# LoRa_ST_v1_0.net
KiCad netlist of a schematic drawn in EAGLE
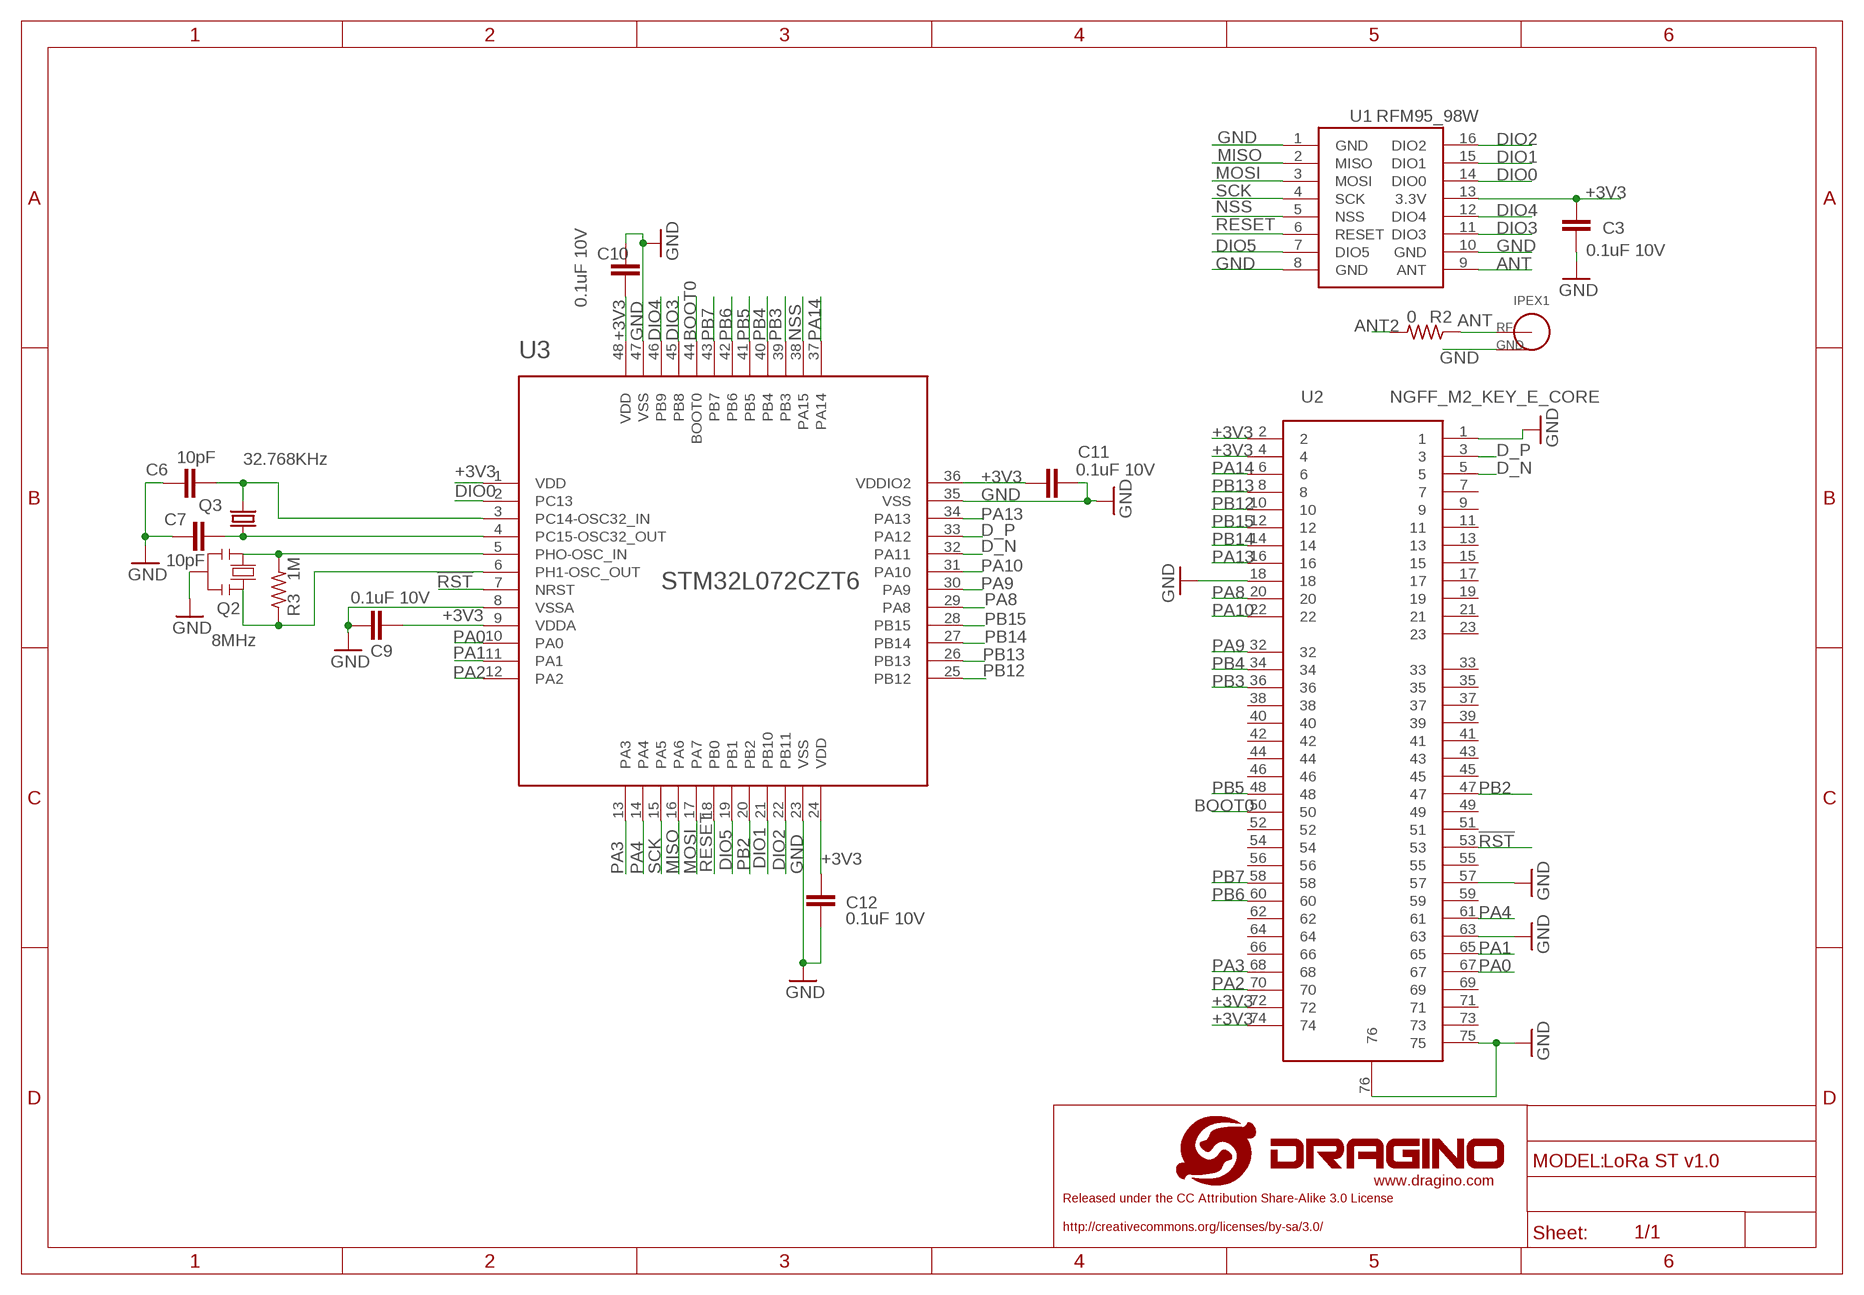
[diagram p0: schematic, sheet 1]

(export (version "E")
  (design (tool "Eeschema 10.0.6"))
  (components
    (comp (ref "C3")
      (value "0.1uF 10V")
      (footprint "eagle-import:C0402")
      (libsource (lib "eagle-import") (part "C-EUC0402"))
    )
    (comp (ref "C6")
      (value "10pF")
      (footprint "eagle-import:C0402")
      (libsource (lib "eagle-import") (part "C-EUC0402"))
    )
    (comp (ref "C7")
      (value "10pF")
      (footprint "eagle-import:C0402")
      (libsource (lib "eagle-import") (part "C-EUC0402"))
    )
    (comp (ref "C9")
      (value "0.1uF 10V")
      (footprint "eagle-import:C0402")
      (libsource (lib "eagle-import") (part "C-EUC0402"))
    )
    (comp (ref "C10")
      (value "0.1uF 10V")
      (footprint "eagle-import:C0402")
      (libsource (lib "eagle-import") (part "C-EUC0402"))
    )
    (comp (ref "C11")
      (value "0.1uF 10V")
      (footprint "eagle-import:C0402")
      (libsource (lib "eagle-import") (part "C-EUC0402"))
    )
    (comp (ref "C12")
      (value "0.1uF 10V")
      (footprint "eagle-import:C0402")
      (libsource (lib "eagle-import") (part "C-EUC0402"))
    )
    (comp (ref "IPEX1")
      (value "I-PEX4")
      (footprint "eagle-import:I-PEX4")
      (libsource (lib "eagle-import") (part "I-PEX4"))
    )
    (comp (ref "Q2")
      (value "8MHz")
      (footprint "eagle-import:RESONATOR")
      (libsource (lib "eagle-import") (part "RESONATORMU"))
    )
    (comp (ref "Q3")
      (value "32.768KHz")
      (footprint "eagle-import:32.768K")
      (libsource (lib "eagle-import") (part "SMD-2012_2P"))
    )
    (comp (ref "R2")
      (value "0")
      (footprint "eagle-import:R0402")
      (libsource (lib "eagle-import") (part "R-US_R0402"))
    )
    (comp (ref "R3")
      (value "1M")
      (footprint "eagle-import:R0402")
      (libsource (lib "eagle-import") (part "R-US_R0402"))
    )
    (comp (ref "U$2")
      (value "LOGO-NEW")
      (footprint "eagle-import:LOGO-SILK-NEW")
      (libsource (lib "eagle-import") (part "LOGO-NEW"))
    )
    (comp (ref "U1")
      (value "RFM95_98W")
      (footprint "eagle-import:RFM95_98W")
      (libsource (lib "eagle-import") (part "RFM95_98W"))
    )
    (comp (ref "U2")
      (value "NGFF_M2_KEY_E_CORE")
      (footprint "eagle-import:LORA_ST_PCB")
      (libsource (lib "eagle-import") (part "NGFF_M2_KEY_E_CORE"))
    )
    (comp (ref "U3")
      (value "STM32L072CZT6")
      (footprint "eagle-import:LQFP48")
      (libsource (lib "eagle-import") (part "STM32L0XX"))
    )
  )
  (nets
    (net (code "1") (name "/+3V3") (class "Default")
      (node (ref "C10") (pin "1") (pinfunction "1_1") (pintype "passive"))
      (node (ref "C11") (pin "2") (pinfunction "2_2") (pintype "passive"))
      (node (ref "C12") (pin "2") (pinfunction "2_2") (pintype "passive"))
      (node (ref "C3") (pin "2") (pinfunction "2_2") (pintype "passive"))
      (node (ref "C9") (pin "1") (pinfunction "1_1") (pintype "passive"))
      (node (ref "U1") (pin "13") (pinfunction "3.3V_13") (pintype "power_in"))
      (node (ref "U2") (pin "2") (pinfunction "2_2") (pintype "bidirectional"))
      (node (ref "U2") (pin "4") (pinfunction "4_4") (pintype "bidirectional"))
      (node (ref "U2") (pin "72") (pinfunction "72_72") (pintype "bidirectional"))
      (node (ref "U2") (pin "74") (pinfunction "74_74") (pintype "bidirectional"))
      (node (ref "U3") (pin "1") (pinfunction "VDD_1") (pintype "bidirectional"))
      (node (ref "U3") (pin "24") (pinfunction "VDD_24") (pintype "bidirectional"))
      (node (ref "U3") (pin "36") (pinfunction "VDDIO2_36") (pintype "bidirectional"))
      (node (ref "U3") (pin "48") (pinfunction "VDD_48") (pintype "bidirectional"))
      (node (ref "U3") (pin "9") (pinfunction "VDDA_9") (pintype "bidirectional"))
    )
    (net (code "2") (name "/ANT") (class "Default")
      (node (ref "IPEX1") (pin "SIG") (pinfunction "SIG_SIG") (pintype "passive"))
      (node (ref "R2") (pin "1") (pinfunction "1_1") (pintype "passive"))
      (node (ref "U1") (pin "9") (pinfunction "ANT_9") (pintype "bidirectional"))
    )
    (net (code "3") (name "/ANT2") (class "Default")
      (node (ref "R2") (pin "2") (pinfunction "2_2") (pintype "passive"))
    )
    (net (code "4") (name "/BOOT0") (class "Default")
      (node (ref "U2") (pin "50") (pinfunction "50_50") (pintype "bidirectional"))
      (node (ref "U3") (pin "44") (pinfunction "BOOT0_44") (pintype "bidirectional"))
    )
    (net (code "5") (name "/DIO0") (class "Default")
      (node (ref "U1") (pin "14") (pinfunction "DIO0_14") (pintype "bidirectional"))
      (node (ref "U3") (pin "2") (pinfunction "PC13_2") (pintype "bidirectional"))
    )
    (net (code "6") (name "/DIO1") (class "Default")
      (node (ref "U1") (pin "15") (pinfunction "DIO1_15") (pintype "bidirectional"))
      (node (ref "U3") (pin "21") (pinfunction "PB10_21") (pintype "bidirectional"))
    )
    (net (code "7") (name "/DIO2") (class "Default")
      (node (ref "U1") (pin "16") (pinfunction "DIO2_16") (pintype "bidirectional"))
      (node (ref "U3") (pin "22") (pinfunction "PB11_22") (pintype "bidirectional"))
    )
    (net (code "8") (name "/DIO3") (class "Default")
      (node (ref "U1") (pin "11") (pinfunction "DIO3_11") (pintype "bidirectional"))
      (node (ref "U3") (pin "45") (pinfunction "PB8_45") (pintype "bidirectional"))
    )
    (net (code "9") (name "/DIO4") (class "Default")
      (node (ref "U1") (pin "12") (pinfunction "DIO4_12") (pintype "bidirectional"))
      (node (ref "U3") (pin "46") (pinfunction "PB9_46") (pintype "bidirectional"))
    )
    (net (code "10") (name "/DIO5") (class "Default")
      (node (ref "U1") (pin "7") (pinfunction "DIO5_7") (pintype "bidirectional"))
      (node (ref "U3") (pin "19") (pinfunction "PB1_19") (pintype "bidirectional"))
    )
    (net (code "11") (name "/D_N") (class "Default")
      (node (ref "U2") (pin "5") (pinfunction "5_5") (pintype "bidirectional"))
      (node (ref "U3") (pin "32") (pinfunction "PA11_32") (pintype "bidirectional"))
    )
    (net (code "12") (name "/D_P") (class "Default")
      (node (ref "U2") (pin "3") (pinfunction "3_3") (pintype "bidirectional"))
      (node (ref "U3") (pin "33") (pinfunction "PA12_33") (pintype "bidirectional"))
    )
    (net (code "13") (name "/MISO") (class "Default")
      (node (ref "U1") (pin "2") (pinfunction "MISO_2") (pintype "bidirectional"))
      (node (ref "U3") (pin "16") (pinfunction "PA6_16") (pintype "bidirectional"))
    )
    (net (code "14") (name "/MOSI") (class "Default")
      (node (ref "U1") (pin "3") (pinfunction "MOSI_3") (pintype "bidirectional"))
      (node (ref "U3") (pin "17") (pinfunction "PA7_17") (pintype "bidirectional"))
    )
    (net (code "15") (name "/NSS") (class "Default")
      (node (ref "U1") (pin "5") (pinfunction "NSS_5") (pintype "bidirectional"))
      (node (ref "U3") (pin "38") (pinfunction "PA15_38") (pintype "bidirectional"))
    )
    (net (code "16") (name "/PA0") (class "Default")
      (node (ref "U2") (pin "67") (pinfunction "67_67") (pintype "bidirectional"))
      (node (ref "U3") (pin "10") (pinfunction "PA0_10") (pintype "bidirectional"))
    )
    (net (code "17") (name "/PA1") (class "Default")
      (node (ref "U2") (pin "65") (pinfunction "65_65") (pintype "bidirectional"))
      (node (ref "U3") (pin "11") (pinfunction "PA1_11") (pintype "bidirectional"))
    )
    (net (code "18") (name "/PA2") (class "Default")
      (node (ref "U2") (pin "70") (pinfunction "70_70") (pintype "bidirectional"))
      (node (ref "U3") (pin "12") (pinfunction "PA2_12") (pintype "bidirectional"))
    )
    (net (code "19") (name "/PA3") (class "Default")
      (node (ref "U2") (pin "68") (pinfunction "68_68") (pintype "bidirectional"))
      (node (ref "U3") (pin "13") (pinfunction "PA3_13") (pintype "bidirectional"))
    )
    (net (code "20") (name "/PA4") (class "Default")
      (node (ref "U2") (pin "61") (pinfunction "61_61") (pintype "bidirectional"))
      (node (ref "U3") (pin "14") (pinfunction "PA4_14") (pintype "bidirectional"))
    )
    (net (code "21") (name "/PA8") (class "Default")
      (node (ref "U2") (pin "20") (pinfunction "20_20") (pintype "bidirectional"))
      (node (ref "U3") (pin "29") (pinfunction "PA8_29") (pintype "bidirectional"))
    )
    (net (code "22") (name "/PA9") (class "Default")
      (node (ref "U2") (pin "32") (pinfunction "32_32") (pintype "bidirectional"))
      (node (ref "U3") (pin "30") (pinfunction "PA9_30") (pintype "bidirectional"))
    )
    (net (code "23") (name "/PA10") (class "Default")
      (node (ref "U2") (pin "22") (pinfunction "22_22") (pintype "bidirectional"))
      (node (ref "U3") (pin "31") (pinfunction "PA10_31") (pintype "bidirectional"))
    )
    (net (code "24") (name "/PA13") (class "Default")
      (node (ref "U2") (pin "16") (pinfunction "16_16") (pintype "bidirectional"))
      (node (ref "U3") (pin "34") (pinfunction "PA13_34") (pintype "bidirectional"))
    )
    (net (code "25") (name "/PA14") (class "Default")
      (node (ref "U2") (pin "6") (pinfunction "6_6") (pintype "bidirectional"))
      (node (ref "U3") (pin "37") (pinfunction "PA14_37") (pintype "bidirectional"))
    )
    (net (code "26") (name "/PB2") (class "Default")
      (node (ref "U2") (pin "47") (pinfunction "47_47") (pintype "bidirectional"))
      (node (ref "U3") (pin "20") (pinfunction "PB2_20") (pintype "bidirectional"))
    )
    (net (code "27") (name "/PB3") (class "Default")
      (node (ref "U2") (pin "36") (pinfunction "36_36") (pintype "bidirectional"))
      (node (ref "U3") (pin "39") (pinfunction "PB3_39") (pintype "bidirectional"))
    )
    (net (code "28") (name "/PB4") (class "Default")
      (node (ref "U2") (pin "34") (pinfunction "34_34") (pintype "bidirectional"))
      (node (ref "U3") (pin "40") (pinfunction "PB4_40") (pintype "bidirectional"))
    )
    (net (code "29") (name "/PB5") (class "Default")
      (node (ref "U2") (pin "48") (pinfunction "48_48") (pintype "bidirectional"))
      (node (ref "U3") (pin "41") (pinfunction "PB5_41") (pintype "bidirectional"))
    )
    (net (code "30") (name "/PB6") (class "Default")
      (node (ref "U2") (pin "60") (pinfunction "60_60") (pintype "bidirectional"))
      (node (ref "U3") (pin "42") (pinfunction "PB6_42") (pintype "bidirectional"))
    )
    (net (code "31") (name "/PB7") (class "Default")
      (node (ref "U2") (pin "58") (pinfunction "58_58") (pintype "bidirectional"))
      (node (ref "U3") (pin "43") (pinfunction "PB7_43") (pintype "bidirectional"))
    )
    (net (code "32") (name "/PB12") (class "Default")
      (node (ref "U2") (pin "10") (pinfunction "10_10") (pintype "bidirectional"))
      (node (ref "U3") (pin "25") (pinfunction "PB12_25") (pintype "bidirectional"))
    )
    (net (code "33") (name "/PB13") (class "Default")
      (node (ref "U2") (pin "8") (pinfunction "8_8") (pintype "bidirectional"))
      (node (ref "U3") (pin "26") (pinfunction "PB13_26") (pintype "bidirectional"))
    )
    (net (code "34") (name "/PB14") (class "Default")
      (node (ref "U2") (pin "14") (pinfunction "14_14") (pintype "bidirectional"))
      (node (ref "U3") (pin "27") (pinfunction "PB14_27") (pintype "bidirectional"))
    )
    (net (code "35") (name "/PB15") (class "Default")
      (node (ref "U2") (pin "12") (pinfunction "12_12") (pintype "bidirectional"))
      (node (ref "U3") (pin "28") (pinfunction "PB15_28") (pintype "bidirectional"))
    )
    (net (code "36") (name "/RESET") (class "Default")
      (node (ref "U1") (pin "6") (pinfunction "RESET_6") (pintype "bidirectional"))
      (node (ref "U3") (pin "18") (pinfunction "PB0_18") (pintype "bidirectional"))
    )
    (net (code "37") (name "/SCK") (class "Default")
      (node (ref "U1") (pin "4") (pinfunction "SCK_4") (pintype "bidirectional"))
      (node (ref "U3") (pin "15") (pinfunction "PA5_15") (pintype "bidirectional"))
    )
    (net (code "38") (name "/~{RST}") (class "Default")
      (node (ref "U2") (pin "53") (pinfunction "53_53") (pintype "bidirectional"))
      (node (ref "U3") (pin "7") (pinfunction "NRST_7") (pintype "bidirectional"))
    )
    (net (code "39") (name "GND") (class "Default")
      (node (ref "C10") (pin "2") (pinfunction "2_2") (pintype "passive"))
      (node (ref "C11") (pin "1") (pinfunction "1_1") (pintype "passive"))
      (node (ref "C12") (pin "1") (pinfunction "1_1") (pintype "passive"))
      (node (ref "C3") (pin "1") (pinfunction "1_1") (pintype "passive"))
      (node (ref "C6") (pin "1") (pinfunction "1_1") (pintype "passive"))
      (node (ref "C7") (pin "1") (pinfunction "1_1") (pintype "passive"))
      (node (ref "C9") (pin "2") (pinfunction "2_2") (pintype "passive"))
      (node (ref "IPEX1") (pin "GND1") (pinfunction "GND_GND1") (pintype "passive"))
      (node (ref "IPEX1") (pin "GND2") (pinfunction "GND_GND2") (pintype "passive"))
      (node (ref "IPEX1") (pin "GND3") (pinfunction "GND_GND3") (pintype "passive"))
      (node (ref "Q2") (pin "2") (pinfunction "2_2") (pintype "passive"))
      (node (ref "U1") (pin "1") (pinfunction "GND_1") (pintype "power_in"))
      (node (ref "U1") (pin "10") (pinfunction "GND_10") (pintype "power_in"))
      (node (ref "U1") (pin "8") (pinfunction "GND_8") (pintype "power_in"))
      (node (ref "U2") (pin "1") (pinfunction "1_1") (pintype "bidirectional"))
      (node (ref "U2") (pin "18") (pinfunction "18_18") (pintype "bidirectional"))
      (node (ref "U2") (pin "57") (pinfunction "57_57") (pintype "bidirectional"))
      (node (ref "U2") (pin "63") (pinfunction "63_63") (pintype "bidirectional"))
      (node (ref "U2") (pin "75") (pinfunction "75_75") (pintype "bidirectional"))
      (node (ref "U2") (pin "76") (pinfunction "76_76") (pintype "bidirectional"))
      (node (ref "U3") (pin "23") (pinfunction "VSS_23") (pintype "bidirectional"))
      (node (ref "U3") (pin "35") (pinfunction "VSS_35") (pintype "bidirectional"))
      (node (ref "U3") (pin "47") (pinfunction "VSS_47") (pintype "bidirectional"))
      (node (ref "U3") (pin "8") (pinfunction "VSSA_8") (pintype "bidirectional"))
    )
    (net (code "40") (name "Net-(Q3-1)") (class "Default")
      (node (ref "C7") (pin "2") (pinfunction "2_2") (pintype "passive"))
      (node (ref "Q3") (pin "3") (pinfunction "1_3") (pintype "passive"))
      (node (ref "U3") (pin "4") (pinfunction "PC15-OSC32_OUT_4") (pintype "bidirectional"))
    )
    (net (code "41") (name "Net-(Q3-2)") (class "Default")
      (node (ref "C6") (pin "2") (pinfunction "2_2") (pintype "passive"))
      (node (ref "Q3") (pin "4") (pinfunction "2_4") (pintype "passive"))
      (node (ref "U3") (pin "3") (pinfunction "PC14-OSC32_IN_3") (pintype "bidirectional"))
    )
    (net (code "42") (name "Net-(U3-PH1-OSC_OUT)") (class "Default")
      (node (ref "Q2") (pin "3") (pinfunction "3_3") (pintype "passive"))
      (node (ref "R3") (pin "1") (pinfunction "1_1") (pintype "passive"))
      (node (ref "U3") (pin "6") (pinfunction "PH1-OSC_OUT_6") (pintype "bidirectional"))
    )
    (net (code "43") (name "Net-(U3-PHO-OSC_IN)") (class "Default")
      (node (ref "Q2") (pin "1") (pinfunction "1_1") (pintype "passive"))
      (node (ref "R3") (pin "2") (pinfunction "2_2") (pintype "passive"))
      (node (ref "U3") (pin "5") (pinfunction "PHO-OSC_IN_5") (pintype "bidirectional"))
    )
    (net (code "44") (name "unconnected-(U2-Pad7)") (class "Default")
      (node (ref "U2") (pin "7") (pinfunction "7_7") (pintype "bidirectional"))
    )
    (net (code "45") (name "unconnected-(U2-Pad9)") (class "Default")
      (node (ref "U2") (pin "9") (pinfunction "9_9") (pintype "bidirectional"))
    )
    (net (code "46") (name "unconnected-(U2-Pad11)") (class "Default")
      (node (ref "U2") (pin "11") (pinfunction "11_11") (pintype "bidirectional"))
    )
    (net (code "47") (name "unconnected-(U2-Pad13)") (class "Default")
      (node (ref "U2") (pin "13") (pinfunction "13_13") (pintype "bidirectional"))
    )
    (net (code "48") (name "unconnected-(U2-Pad15)") (class "Default")
      (node (ref "U2") (pin "15") (pinfunction "15_15") (pintype "bidirectional"))
    )
    (net (code "49") (name "unconnected-(U2-Pad17)") (class "Default")
      (node (ref "U2") (pin "17") (pinfunction "17_17") (pintype "bidirectional"))
    )
    (net (code "50") (name "unconnected-(U2-Pad19)") (class "Default")
      (node (ref "U2") (pin "19") (pinfunction "19_19") (pintype "bidirectional"))
    )
    (net (code "51") (name "unconnected-(U2-Pad21)") (class "Default")
      (node (ref "U2") (pin "21") (pinfunction "21_21") (pintype "bidirectional"))
    )
    (net (code "52") (name "unconnected-(U2-Pad23)") (class "Default")
      (node (ref "U2") (pin "23") (pinfunction "23_23") (pintype "bidirectional"))
    )
    (net (code "53") (name "unconnected-(U2-Pad33)") (class "Default")
      (node (ref "U2") (pin "33") (pinfunction "33_33") (pintype "bidirectional"))
    )
    (net (code "54") (name "unconnected-(U2-Pad35)") (class "Default")
      (node (ref "U2") (pin "35") (pinfunction "35_35") (pintype "bidirectional"))
    )
    (net (code "55") (name "unconnected-(U2-Pad37)") (class "Default")
      (node (ref "U2") (pin "37") (pinfunction "37_37") (pintype "bidirectional"))
    )
    (net (code "56") (name "unconnected-(U2-Pad38)") (class "Default")
      (node (ref "U2") (pin "38") (pinfunction "38_38") (pintype "bidirectional"))
    )
    (net (code "57") (name "unconnected-(U2-Pad39)") (class "Default")
      (node (ref "U2") (pin "39") (pinfunction "39_39") (pintype "bidirectional"))
    )
    (net (code "58") (name "unconnected-(U2-Pad40)") (class "Default")
      (node (ref "U2") (pin "40") (pinfunction "40_40") (pintype "bidirectional"))
    )
    (net (code "59") (name "unconnected-(U2-Pad41)") (class "Default")
      (node (ref "U2") (pin "41") (pinfunction "41_41") (pintype "bidirectional"))
    )
    (net (code "60") (name "unconnected-(U2-Pad42)") (class "Default")
      (node (ref "U2") (pin "42") (pinfunction "42_42") (pintype "bidirectional"))
    )
    (net (code "61") (name "unconnected-(U2-Pad43)") (class "Default")
      (node (ref "U2") (pin "43") (pinfunction "43_43") (pintype "bidirectional"))
    )
    (net (code "62") (name "unconnected-(U2-Pad44)") (class "Default")
      (node (ref "U2") (pin "44") (pinfunction "44_44") (pintype "bidirectional"))
    )
    (net (code "63") (name "unconnected-(U2-Pad45)") (class "Default")
      (node (ref "U2") (pin "45") (pinfunction "45_45") (pintype "bidirectional"))
    )
    (net (code "64") (name "unconnected-(U2-Pad46)") (class "Default")
      (node (ref "U2") (pin "46") (pinfunction "46_46") (pintype "bidirectional"))
    )
    (net (code "65") (name "unconnected-(U2-Pad49)") (class "Default")
      (node (ref "U2") (pin "49") (pinfunction "49_49") (pintype "bidirectional"))
    )
    (net (code "66") (name "unconnected-(U2-Pad51)") (class "Default")
      (node (ref "U2") (pin "51") (pinfunction "51_51") (pintype "bidirectional"))
    )
    (net (code "67") (name "unconnected-(U2-Pad52)") (class "Default")
      (node (ref "U2") (pin "52") (pinfunction "52_52") (pintype "bidirectional"))
    )
    (net (code "68") (name "unconnected-(U2-Pad54)") (class "Default")
      (node (ref "U2") (pin "54") (pinfunction "54_54") (pintype "bidirectional"))
    )
    (net (code "69") (name "unconnected-(U2-Pad55)") (class "Default")
      (node (ref "U2") (pin "55") (pinfunction "55_55") (pintype "bidirectional"))
    )
    (net (code "70") (name "unconnected-(U2-Pad56)") (class "Default")
      (node (ref "U2") (pin "56") (pinfunction "56_56") (pintype "bidirectional"))
    )
    (net (code "71") (name "unconnected-(U2-Pad59)") (class "Default")
      (node (ref "U2") (pin "59") (pinfunction "59_59") (pintype "bidirectional"))
    )
    (net (code "72") (name "unconnected-(U2-Pad62)") (class "Default")
      (node (ref "U2") (pin "62") (pinfunction "62_62") (pintype "bidirectional"))
    )
    (net (code "73") (name "unconnected-(U2-Pad64)") (class "Default")
      (node (ref "U2") (pin "64") (pinfunction "64_64") (pintype "bidirectional"))
    )
    (net (code "74") (name "unconnected-(U2-Pad66)") (class "Default")
      (node (ref "U2") (pin "66") (pinfunction "66_66") (pintype "bidirectional"))
    )
    (net (code "75") (name "unconnected-(U2-Pad69)") (class "Default")
      (node (ref "U2") (pin "69") (pinfunction "69_69") (pintype "bidirectional"))
    )
    (net (code "76") (name "unconnected-(U2-Pad71)") (class "Default")
      (node (ref "U2") (pin "71") (pinfunction "71_71") (pintype "bidirectional"))
    )
    (net (code "77") (name "unconnected-(U2-Pad73)") (class "Default")
      (node (ref "U2") (pin "73") (pinfunction "73_73") (pintype "bidirectional"))
    )
  )
)
